# FilterControl_Schematic.net
KiCad netlist of a schematic drawn in Altium Designer
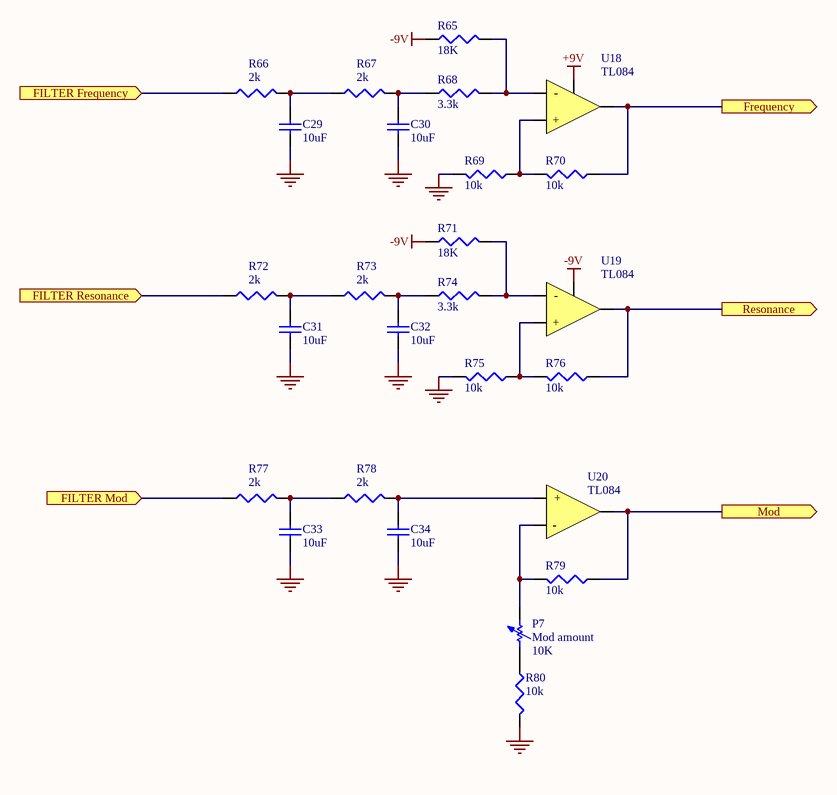
[diagram p0: FilterControl.Schematic.SchDoc]

(export (version "E")
  (design (tool "Eeschema 10.0.6"))
  (components
    (comp (ref "C29")
      (value "10uF")
      (footprint "CAPC1608N")
      (description "Capacitor (Semiconductor SIM Model)")
      (fields (field (name "PUBLISHER") "Altium Limited"))
      (libsource (lib "Miscellaneous Devices") (part "Cap Semi"))
    )
    (comp (ref "C30")
      (value "10uF")
      (footprint "CAPC1608N")
      (description "Capacitor (Semiconductor SIM Model)")
      (fields (field (name "PUBLISHER") "Altium Limited"))
      (libsource (lib "Miscellaneous Devices") (part "Cap Semi"))
    )
    (comp (ref "C31")
      (value "10uF")
      (footprint "CAPC1608N")
      (description "Capacitor (Semiconductor SIM Model)")
      (fields (field (name "PUBLISHER") "Altium Limited"))
      (libsource (lib "Miscellaneous Devices") (part "Cap Semi"))
    )
    (comp (ref "C32")
      (value "10uF")
      (footprint "CAPC1608N")
      (description "Capacitor (Semiconductor SIM Model)")
      (fields (field (name "PUBLISHER") "Altium Limited"))
      (libsource (lib "Miscellaneous Devices") (part "Cap Semi"))
    )
    (comp (ref "C33")
      (value "10uF")
      (footprint "CAPC1608N")
      (description "Capacitor (Semiconductor SIM Model)")
      (fields (field (name "PUBLISHER") "Altium Limited"))
      (libsource (lib "Miscellaneous Devices") (part "Cap Semi"))
    )
    (comp (ref "C34")
      (value "10uF")
      (footprint "CAPC1608N")
      (description "Capacitor (Semiconductor SIM Model)")
      (fields (field (name "PUBLISHER") "Altium Limited"))
      (libsource (lib "Miscellaneous Devices") (part "Cap Semi"))
    )
    (comp (ref "P7")
      (value "Mod amount")
      (footprint "AXIAL-0.7")
      (description "Variable Resistor")
      (fields (field (name "ALTIUM_VALUE") "10K") (field (name "PUBLISHER") "Altium Limited"))
      (libsource (lib "Miscellaneous Devices") (part "Res Adj1"))
    )
    (comp (ref "R65")
      (value "18K")
      (footprint "CAPC1608N")
      (description "Resistor")
      (fields (field (name "PUBLISHER") "Altium Limited"))
      (libsource (lib "Miscellaneous Devices") (part "Res3"))
    )
    (comp (ref "R66")
      (value "2k")
      (footprint "CAPC1608N")
      (description "Resistor")
      (fields (field (name "PUBLISHER") "Altium Limited"))
      (libsource (lib "Miscellaneous Devices") (part "Res3"))
    )
    (comp (ref "R67")
      (value "2k")
      (footprint "CAPC1608N")
      (description "Resistor")
      (fields (field (name "PUBLISHER") "Altium Limited"))
      (libsource (lib "Miscellaneous Devices") (part "Res3"))
    )
    (comp (ref "R68")
      (value "3.3k")
      (footprint "CAPC1608N")
      (description "Resistor")
      (fields (field (name "PUBLISHER") "Altium Limited"))
      (libsource (lib "Miscellaneous Devices") (part "Res3"))
    )
    (comp (ref "R69")
      (value "10k")
      (footprint "CAPC1608N")
      (description "Resistor")
      (fields (field (name "PUBLISHER") "Altium Limited"))
      (libsource (lib "Miscellaneous Devices") (part "Res3"))
    )
    (comp (ref "R70")
      (value "10k")
      (footprint "CAPC1608N")
      (description "Resistor")
      (fields (field (name "PUBLISHER") "Altium Limited"))
      (libsource (lib "Miscellaneous Devices") (part "Res3"))
    )
    (comp (ref "R71")
      (value "18K")
      (footprint "CAPC1608N")
      (description "Resistor")
      (fields (field (name "PUBLISHER") "Altium Limited"))
      (libsource (lib "Miscellaneous Devices") (part "Res3"))
    )
    (comp (ref "R72")
      (value "2k")
      (footprint "CAPC1608N")
      (description "Resistor")
      (fields (field (name "PUBLISHER") "Altium Limited"))
      (libsource (lib "Miscellaneous Devices") (part "Res3"))
    )
    (comp (ref "R73")
      (value "2k")
      (footprint "CAPC1608N")
      (description "Resistor")
      (fields (field (name "PUBLISHER") "Altium Limited"))
      (libsource (lib "Miscellaneous Devices") (part "Res3"))
    )
    (comp (ref "R74")
      (value "3.3k")
      (footprint "CAPC1608N")
      (description "Resistor")
      (fields (field (name "PUBLISHER") "Altium Limited"))
      (libsource (lib "Miscellaneous Devices") (part "Res3"))
    )
    (comp (ref "R75")
      (value "10k")
      (footprint "CAPC1608N")
      (description "Resistor")
      (fields (field (name "PUBLISHER") "Altium Limited"))
      (libsource (lib "Miscellaneous Devices") (part "Res3"))
    )
    (comp (ref "R76")
      (value "10k")
      (footprint "CAPC1608N")
      (description "Resistor")
      (fields (field (name "PUBLISHER") "Altium Limited"))
      (libsource (lib "Miscellaneous Devices") (part "Res3"))
    )
    (comp (ref "R77")
      (value "2k")
      (footprint "CAPC1608N")
      (description "Resistor")
      (fields (field (name "PUBLISHER") "Altium Limited"))
      (libsource (lib "Miscellaneous Devices") (part "Res3"))
    )
    (comp (ref "R78")
      (value "2k")
      (footprint "CAPC1608N")
      (description "Resistor")
      (fields (field (name "PUBLISHER") "Altium Limited"))
      (libsource (lib "Miscellaneous Devices") (part "Res3"))
    )
    (comp (ref "R79")
      (value "10k")
      (footprint "CAPC1608N")
      (description "Resistor")
      (fields (field (name "PUBLISHER") "Altium Limited"))
      (libsource (lib "Miscellaneous Devices") (part "Res3"))
    )
    (comp (ref "R80")
      (value "10k")
      (footprint "CAPC1608N")
      (description "Resistor")
      (fields (field (name "PUBLISHER") "Altium Limited"))
      (libsource (lib "Miscellaneous Devices") (part "Res3"))
    )
    (comp (ref "U18")
      (value "TL084")
      (footprint "TL084_3PADS+ALIM")
      (libsource (lib "SynthyTwo.Components") (part "TL084"))
    )
    (comp (ref "U19")
      (value "TL084")
      (footprint "TL084_3PADS+ALIM")
      (libsource (lib "SynthyTwo.Components") (part "TL084"))
    )
    (comp (ref "U20") (value "TL084") (footprint "TL084_3PADS") (libsource (lib "") (part "TL084_1")))
  )
  (nets
    (net (code "1") (name "+9V") (class "Default")
      (node (ref "U18") (pin "4") (pinfunction "VCC+_4") (pintype "passive"))
    )
    (net (code "2") (name "-9V") (class "Default")
      (node (ref "R65") (pin "1") (pinfunction "1_1") (pintype "passive"))
      (node (ref "R71") (pin "1") (pinfunction "1_1") (pintype "passive"))
      (node (ref "U19") (pin "4") (pinfunction "VCC+_4") (pintype "passive"))
    )
    (net (code "3") (name "/FILTER Frequency") (class "Default")
      (node (ref "R66") (pin "1") (pinfunction "1_1") (pintype "passive"))
    )
    (net (code "4") (name "/FILTER Mod") (class "Default")
      (node (ref "R77") (pin "1") (pinfunction "1_1") (pintype "passive"))
    )
    (net (code "5") (name "/FILTER Resonance") (class "Default")
      (node (ref "R72") (pin "1") (pinfunction "1_1") (pintype "passive"))
    )
    (net (code "6") (name "/Frequency") (class "Default")
      (node (ref "R70") (pin "1") (pinfunction "1_1") (pintype "passive"))
      (node (ref "U18") (pin "1") (pinfunction "OUT_1") (pintype "passive"))
    )
    (net (code "7") (name "/Mod") (class "Default")
      (node (ref "R79") (pin "1") (pinfunction "1_1") (pintype "passive"))
      (node (ref "U20") (pin "1") (pinfunction "OUT_1") (pintype "passive"))
    )
    (net (code "8") (name "/Resonance") (class "Default")
      (node (ref "R76") (pin "1") (pinfunction "1_1") (pintype "passive"))
      (node (ref "U19") (pin "1") (pinfunction "OUT_1") (pintype "passive"))
    )
    (net (code "9") (name "GND") (class "Default")
      (node (ref "C29") (pin "1") (pinfunction "1_1") (pintype "passive"))
      (node (ref "C30") (pin "1") (pinfunction "1_1") (pintype "passive"))
      (node (ref "C31") (pin "1") (pinfunction "1_1") (pintype "passive"))
      (node (ref "C32") (pin "1") (pinfunction "1_1") (pintype "passive"))
      (node (ref "C33") (pin "1") (pinfunction "1_1") (pintype "passive"))
      (node (ref "C34") (pin "1") (pinfunction "1_1") (pintype "passive"))
      (node (ref "R69") (pin "2") (pinfunction "2_2") (pintype "passive"))
      (node (ref "R75") (pin "2") (pinfunction "2_2") (pintype "passive"))
      (node (ref "R80") (pin "2") (pinfunction "2_2") (pintype "passive"))
    )
    (net (code "10") (name "Net-(C29-Pad2)") (class "Default")
      (node (ref "C29") (pin "2") (pinfunction "2_2") (pintype "passive"))
      (node (ref "R66") (pin "2") (pinfunction "2_2") (pintype "passive"))
      (node (ref "R67") (pin "1") (pinfunction "1_1") (pintype "passive"))
    )
    (net (code "11") (name "Net-(C30-Pad2)") (class "Default")
      (node (ref "C30") (pin "2") (pinfunction "2_2") (pintype "passive"))
      (node (ref "R67") (pin "2") (pinfunction "2_2") (pintype "passive"))
      (node (ref "R68") (pin "1") (pinfunction "1_1") (pintype "passive"))
    )
    (net (code "12") (name "Net-(C31-Pad2)") (class "Default")
      (node (ref "C31") (pin "2") (pinfunction "2_2") (pintype "passive"))
      (node (ref "R72") (pin "2") (pinfunction "2_2") (pintype "passive"))
      (node (ref "R73") (pin "1") (pinfunction "1_1") (pintype "passive"))
    )
    (net (code "13") (name "Net-(C32-Pad2)") (class "Default")
      (node (ref "C32") (pin "2") (pinfunction "2_2") (pintype "passive"))
      (node (ref "R73") (pin "2") (pinfunction "2_2") (pintype "passive"))
      (node (ref "R74") (pin "1") (pinfunction "1_1") (pintype "passive"))
    )
    (net (code "14") (name "Net-(C33-Pad2)") (class "Default")
      (node (ref "C33") (pin "2") (pinfunction "2_2") (pintype "passive"))
      (node (ref "R77") (pin "2") (pinfunction "2_2") (pintype "passive"))
      (node (ref "R78") (pin "1") (pinfunction "1_1") (pintype "passive"))
    )
    (net (code "15") (name "Net-(P7-Pad1)") (class "Default")
      (node (ref "P7") (pin "1") (pinfunction "1_1") (pintype "passive"))
      (node (ref "R80") (pin "1") (pinfunction "1_1") (pintype "passive"))
    )
    (net (code "16") (name "Net-(U18-+)") (class "Default")
      (node (ref "R69") (pin "1") (pinfunction "1_1") (pintype "passive"))
      (node (ref "R70") (pin "2") (pinfunction "2_2") (pintype "passive"))
      (node (ref "U18") (pin "3") (pinfunction "+_3") (pintype "passive"))
    )
    (net (code "17") (name "Net-(U18--)") (class "Default")
      (node (ref "R65") (pin "2") (pinfunction "2_2") (pintype "passive"))
      (node (ref "R68") (pin "2") (pinfunction "2_2") (pintype "passive"))
      (node (ref "U18") (pin "2") (pinfunction "-_2") (pintype "passive"))
    )
    (net (code "18") (name "Net-(U19-+)") (class "Default")
      (node (ref "R75") (pin "1") (pinfunction "1_1") (pintype "passive"))
      (node (ref "R76") (pin "2") (pinfunction "2_2") (pintype "passive"))
      (node (ref "U19") (pin "3") (pinfunction "+_3") (pintype "passive"))
    )
    (net (code "19") (name "Net-(U19--)") (class "Default")
      (node (ref "R71") (pin "2") (pinfunction "2_2") (pintype "passive"))
      (node (ref "R74") (pin "2") (pinfunction "2_2") (pintype "passive"))
      (node (ref "U19") (pin "2") (pinfunction "-_2") (pintype "passive"))
    )
    (net (code "20") (name "Net-(U20-+)") (class "Default")
      (node (ref "C34") (pin "2") (pinfunction "2_2") (pintype "passive"))
      (node (ref "R78") (pin "2") (pinfunction "2_2") (pintype "passive"))
      (node (ref "U20") (pin "3") (pinfunction "+_3") (pintype "passive"))
    )
    (net (code "21") (name "Net-(U20--)") (class "Default")
      (node (ref "P7") (pin "2") (pinfunction "2_2") (pintype "passive"))
      (node (ref "R79") (pin "2") (pinfunction "2_2") (pintype "passive"))
      (node (ref "U20") (pin "2") (pinfunction "-_2") (pintype "passive"))
    )
  )
)
